# rpi_pico.net
KiCad netlist of a schematic drawn in Altium Designer
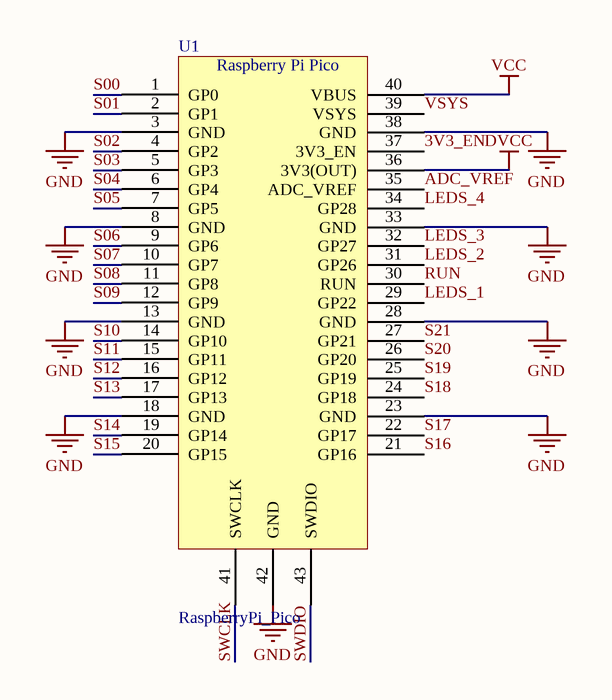
[diagram p0: rpi_pico.SchDoc]

(export (version "E")
  (design (tool "Eeschema 10.0.6"))
  (components
    (comp (ref "U1")
      (value "RaspberryPi_Pico")
      (footprint "PiPico_Holes")
      (libsource (lib "Schlib1") (part "RaspberryPi_Pico"))
    )
  )
  (nets
    (net (code "1") (name "/3V3_EN") (class "Default")
      (node (ref "U1") (pin "37") (pinfunction "3V3_EN_37") (pintype "passive"))
    )
    (net (code "2") (name "/ADC_VREF") (class "Default")
      (node (ref "U1") (pin "35") (pinfunction "ADC_VREF_35") (pintype "passive"))
    )
    (net (code "3") (name "/LEDS_1") (class "Default")
      (node (ref "U1") (pin "29") (pinfunction "GP22_29") (pintype "passive"))
    )
    (net (code "4") (name "/LEDS_2") (class "Default")
      (node (ref "U1") (pin "31") (pinfunction "GP26_31") (pintype "passive"))
    )
    (net (code "5") (name "/LEDS_3") (class "Default")
      (node (ref "U1") (pin "32") (pinfunction "GP27_32") (pintype "passive"))
    )
    (net (code "6") (name "/LEDS_4") (class "Default")
      (node (ref "U1") (pin "34") (pinfunction "GP28_34") (pintype "passive"))
    )
    (net (code "7") (name "/RUN") (class "Default")
      (node (ref "U1") (pin "30") (pinfunction "RUN_30") (pintype "passive"))
    )
    (net (code "8") (name "/S00") (class "Default")
      (node (ref "U1") (pin "1") (pinfunction "GP0_1") (pintype "passive"))
    )
    (net (code "9") (name "/S01") (class "Default")
      (node (ref "U1") (pin "2") (pinfunction "GP1_2") (pintype "passive"))
    )
    (net (code "10") (name "/S02") (class "Default")
      (node (ref "U1") (pin "4") (pinfunction "GP2_4") (pintype "passive"))
    )
    (net (code "11") (name "/S03") (class "Default")
      (node (ref "U1") (pin "5") (pinfunction "GP3_5") (pintype "passive"))
    )
    (net (code "12") (name "/S04") (class "Default")
      (node (ref "U1") (pin "6") (pinfunction "GP4_6") (pintype "passive"))
    )
    (net (code "13") (name "/S05") (class "Default")
      (node (ref "U1") (pin "7") (pinfunction "GP5_7") (pintype "passive"))
    )
    (net (code "14") (name "/S06") (class "Default")
      (node (ref "U1") (pin "9") (pinfunction "GP6_9") (pintype "passive"))
    )
    (net (code "15") (name "/S07") (class "Default")
      (node (ref "U1") (pin "10") (pinfunction "GP7_10") (pintype "passive"))
    )
    (net (code "16") (name "/S08") (class "Default")
      (node (ref "U1") (pin "11") (pinfunction "GP8_11") (pintype "passive"))
    )
    (net (code "17") (name "/S09") (class "Default")
      (node (ref "U1") (pin "12") (pinfunction "GP9_12") (pintype "passive"))
    )
    (net (code "18") (name "/S10") (class "Default")
      (node (ref "U1") (pin "14") (pinfunction "GP10_14") (pintype "passive"))
    )
    (net (code "19") (name "/S11") (class "Default")
      (node (ref "U1") (pin "15") (pinfunction "GP11_15") (pintype "passive"))
    )
    (net (code "20") (name "/S12") (class "Default")
      (node (ref "U1") (pin "16") (pinfunction "GP12_16") (pintype "passive"))
    )
    (net (code "21") (name "/S13") (class "Default")
      (node (ref "U1") (pin "17") (pinfunction "GP13_17") (pintype "passive"))
    )
    (net (code "22") (name "/S14") (class "Default")
      (node (ref "U1") (pin "19") (pinfunction "GP14_19") (pintype "passive"))
    )
    (net (code "23") (name "/S15") (class "Default")
      (node (ref "U1") (pin "20") (pinfunction "GP15_20") (pintype "passive"))
    )
    (net (code "24") (name "/S16") (class "Default")
      (node (ref "U1") (pin "21") (pinfunction "GP16_21") (pintype "passive"))
    )
    (net (code "25") (name "/S17") (class "Default")
      (node (ref "U1") (pin "22") (pinfunction "GP17_22") (pintype "passive"))
    )
    (net (code "26") (name "/S18") (class "Default")
      (node (ref "U1") (pin "24") (pinfunction "GP18_24") (pintype "passive"))
    )
    (net (code "27") (name "/S19") (class "Default")
      (node (ref "U1") (pin "25") (pinfunction "GP19_25") (pintype "passive"))
    )
    (net (code "28") (name "/S20") (class "Default")
      (node (ref "U1") (pin "26") (pinfunction "GP20_26") (pintype "passive"))
    )
    (net (code "29") (name "/S21") (class "Default")
      (node (ref "U1") (pin "27") (pinfunction "GP21_27") (pintype "passive"))
    )
    (net (code "30") (name "/SWCLK") (class "Default")
      (node (ref "U1") (pin "41") (pinfunction "SWCLK_41") (pintype "passive"))
    )
    (net (code "31") (name "/SWDIO") (class "Default")
      (node (ref "U1") (pin "43") (pinfunction "SWDIO_43") (pintype "passive"))
    )
    (net (code "32") (name "/VSYS") (class "Default")
      (node (ref "U1") (pin "39") (pinfunction "VSYS_39") (pintype "passive"))
    )
    (net (code "33") (name "DVCC") (class "Default")
      (node (ref "U1") (pin "36") (pinfunction "3V3(OUT)_36") (pintype "passive"))
    )
    (net (code "34") (name "GND") (class "Default")
      (node (ref "U1") (pin "13") (pinfunction "GND_13") (pintype "passive"))
      (node (ref "U1") (pin "18") (pinfunction "GND_18") (pintype "passive"))
      (node (ref "U1") (pin "23") (pinfunction "GND_23") (pintype "passive"))
      (node (ref "U1") (pin "28") (pinfunction "GND_28") (pintype "passive"))
      (node (ref "U1") (pin "3") (pinfunction "GND_3") (pintype "passive"))
      (node (ref "U1") (pin "33") (pinfunction "GND_33") (pintype "passive"))
      (node (ref "U1") (pin "38") (pinfunction "GND_38") (pintype "passive"))
      (node (ref "U1") (pin "42") (pinfunction "GND_42") (pintype "passive"))
      (node (ref "U1") (pin "8") (pinfunction "GND_8") (pintype "passive"))
    )
    (net (code "35") (name "VCC") (class "Default")
      (node (ref "U1") (pin "40") (pinfunction "VBUS_40") (pintype "passive"))
    )
  )
)
